# RPi.net
KiCad netlist of a schematic drawn in EAGLE
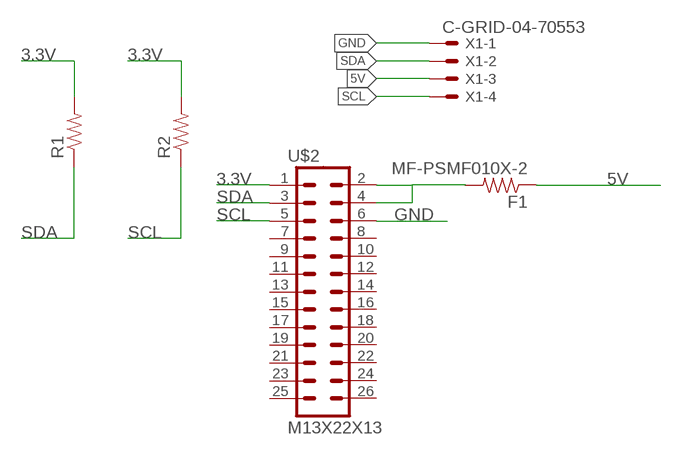
[diagram p0: schematic, sheet 1]

(export (version "E")
  (design (tool "Eeschema 10.0.6"))
  (components
    (comp (ref "F1")
      (value "MF-PSMF010X-2")
      (footprint "eagle-import:0805")
      (libsource (lib "eagle-import") (part "RESISTOR0805-RES"))
    )
    (comp (ref "R1")
      (value "RESISTOR0805-RES")
      (footprint "eagle-import:0805")
      (libsource (lib "eagle-import") (part "RESISTOR0805-RES"))
    )
    (comp (ref "R2")
      (value "RESISTOR0805-RES")
      (footprint "eagle-import:0805")
      (libsource (lib "eagle-import") (part "RESISTOR0805-RES"))
    )
    (comp (ref "U$2")
      (value "M13X22X13")
      (footprint "eagle-import:2X13")
      (libsource (lib "eagle-import") (part "M13X22X13"))
    )
    (comp (ref "X1")
      (value "C-GRID-04-70553")
      (footprint "eagle-import:70553-04")
      (libsource (lib "eagle-import") (part "C-GRID-04-70553"))
    )
  )
  (nets
    (net (code "1") (name "/3.3V") (class "Default")
      (node (ref "R1") (pin "2") (pinfunction "2_2") (pintype "passive"))
      (node (ref "R2") (pin "2") (pinfunction "2_2") (pintype "passive"))
      (node (ref "U$2") (pin "1") (pinfunction "1_1") (pintype "passive"))
    )
    (net (code "2") (name "5V") (class "Default")
      (node (ref "F1") (pin "1") (pinfunction "1_1") (pintype "passive"))
      (node (ref "X1") (pin "3") (pinfunction "S_3") (pintype "passive"))
    )
    (net (code "3") (name "GND") (class "Default")
      (node (ref "U$2") (pin "6") (pinfunction "6_6") (pintype "passive"))
      (node (ref "X1") (pin "1") (pinfunction "S_1") (pintype "passive"))
    )
    (net (code "4") (name "Net-(F1-Pad2)") (class "Default")
      (node (ref "F1") (pin "2") (pinfunction "2_2") (pintype "passive"))
      (node (ref "U$2") (pin "2") (pinfunction "2_2") (pintype "passive"))
      (node (ref "U$2") (pin "4") (pinfunction "4_4") (pintype "passive"))
    )
    (net (code "5") (name "SCL") (class "Default")
      (node (ref "R2") (pin "1") (pinfunction "1_1") (pintype "passive"))
      (node (ref "U$2") (pin "5") (pinfunction "5_5") (pintype "passive"))
      (node (ref "X1") (pin "4") (pinfunction "S_4") (pintype "passive"))
    )
    (net (code "6") (name "SDA") (class "Default")
      (node (ref "R1") (pin "1") (pinfunction "1_1") (pintype "passive"))
      (node (ref "U$2") (pin "3") (pinfunction "3_3") (pintype "passive"))
      (node (ref "X1") (pin "2") (pinfunction "S_2") (pintype "passive"))
    )
    (net (code "7") (name "unconnected-(U$2-Pad7)") (class "Default")
      (node (ref "U$2") (pin "7") (pinfunction "7_7") (pintype "passive"))
    )
    (net (code "8") (name "unconnected-(U$2-Pad8)") (class "Default")
      (node (ref "U$2") (pin "8") (pinfunction "8_8") (pintype "passive"))
    )
    (net (code "9") (name "unconnected-(U$2-Pad9)") (class "Default")
      (node (ref "U$2") (pin "9") (pinfunction "9_9") (pintype "passive"))
    )
    (net (code "10") (name "unconnected-(U$2-Pad10)") (class "Default")
      (node (ref "U$2") (pin "10") (pinfunction "10_10") (pintype "passive"))
    )
    (net (code "11") (name "unconnected-(U$2-Pad11)") (class "Default")
      (node (ref "U$2") (pin "11") (pinfunction "11_11") (pintype "passive"))
    )
    (net (code "12") (name "unconnected-(U$2-Pad12)") (class "Default")
      (node (ref "U$2") (pin "12") (pinfunction "12_12") (pintype "passive"))
    )
    (net (code "13") (name "unconnected-(U$2-Pad13)") (class "Default")
      (node (ref "U$2") (pin "13") (pinfunction "13_13") (pintype "passive"))
    )
    (net (code "14") (name "unconnected-(U$2-Pad14)") (class "Default")
      (node (ref "U$2") (pin "14") (pinfunction "14_14") (pintype "passive"))
    )
    (net (code "15") (name "unconnected-(U$2-Pad15)") (class "Default")
      (node (ref "U$2") (pin "15") (pinfunction "15_15") (pintype "passive"))
    )
    (net (code "16") (name "unconnected-(U$2-Pad16)") (class "Default")
      (node (ref "U$2") (pin "16") (pinfunction "16_16") (pintype "passive"))
    )
    (net (code "17") (name "unconnected-(U$2-Pad17)") (class "Default")
      (node (ref "U$2") (pin "17") (pinfunction "17_17") (pintype "passive"))
    )
    (net (code "18") (name "unconnected-(U$2-Pad18)") (class "Default")
      (node (ref "U$2") (pin "18") (pinfunction "18_18") (pintype "passive"))
    )
    (net (code "19") (name "unconnected-(U$2-Pad19)") (class "Default")
      (node (ref "U$2") (pin "19") (pinfunction "19_19") (pintype "passive"))
    )
    (net (code "20") (name "unconnected-(U$2-Pad20)") (class "Default")
      (node (ref "U$2") (pin "20") (pinfunction "20_20") (pintype "passive"))
    )
    (net (code "21") (name "unconnected-(U$2-Pad21)") (class "Default")
      (node (ref "U$2") (pin "21") (pinfunction "21_21") (pintype "passive"))
    )
    (net (code "22") (name "unconnected-(U$2-Pad22)") (class "Default")
      (node (ref "U$2") (pin "22") (pinfunction "22_22") (pintype "passive"))
    )
    (net (code "23") (name "unconnected-(U$2-Pad23)") (class "Default")
      (node (ref "U$2") (pin "23") (pinfunction "23_23") (pintype "passive"))
    )
    (net (code "24") (name "unconnected-(U$2-Pad24)") (class "Default")
      (node (ref "U$2") (pin "24") (pinfunction "24_24") (pintype "passive"))
    )
    (net (code "25") (name "unconnected-(U$2-Pad25)") (class "Default")
      (node (ref "U$2") (pin "25") (pinfunction "25_25") (pintype "passive"))
    )
    (net (code "26") (name "unconnected-(U$2-Pad26)") (class "Default")
      (node (ref "U$2") (pin "26") (pinfunction "26_26") (pintype "passive"))
    )
  )
)
